# RemoteControlPowerBoard.net
KiCad netlist of a schematic drawn in Altium Designer
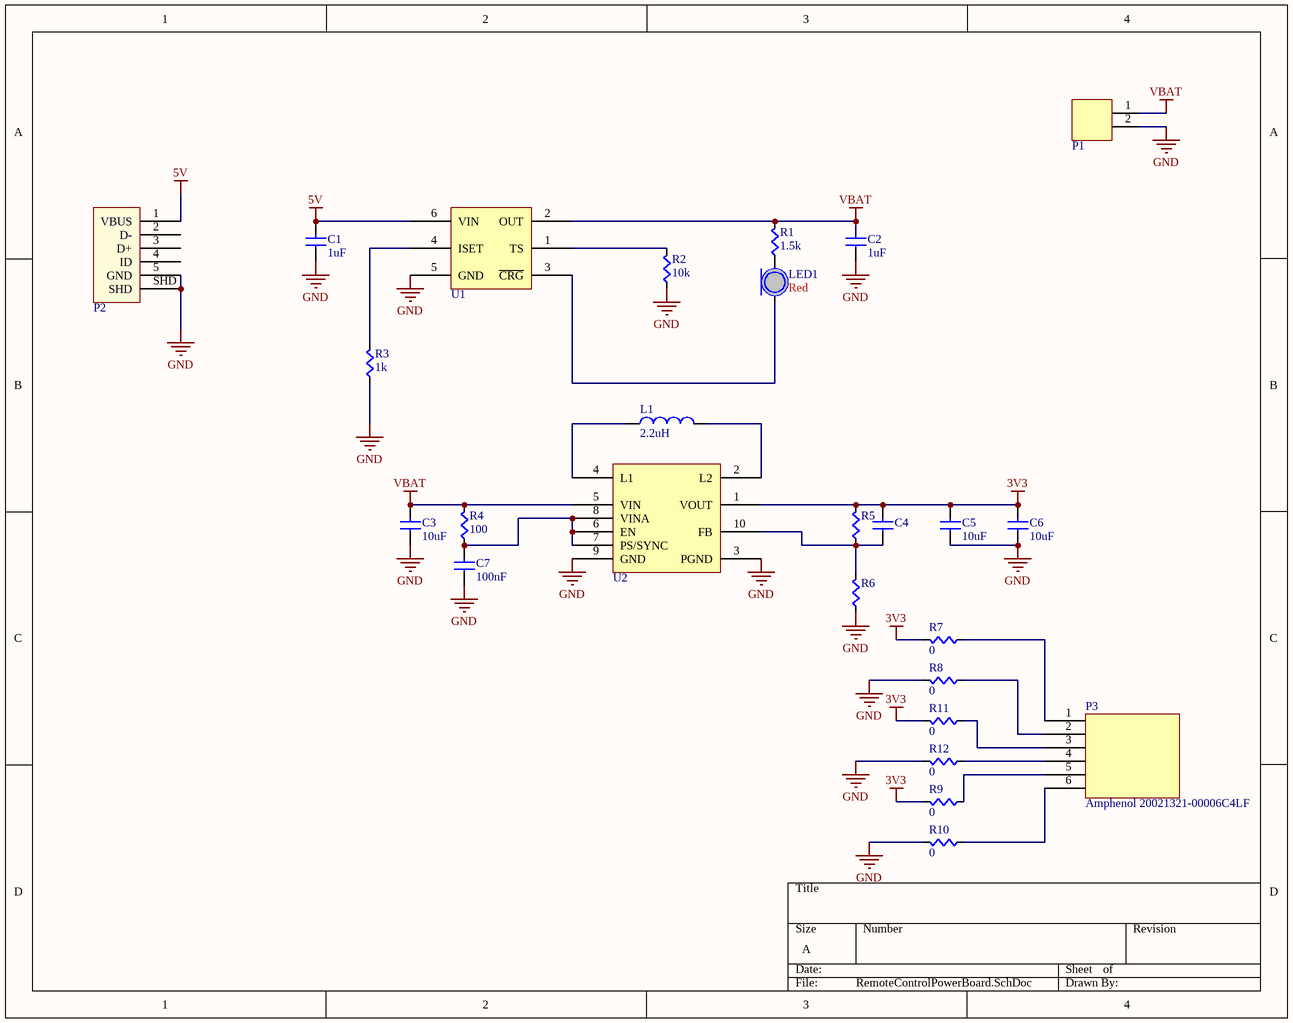
[diagram p0: RemoteControlPowerBoard.SchDoc]

(export (version "E")
  (design (tool "Eeschema 10.0.6"))
  (components
    (comp (ref "C1")
      (value "1uF")
      (footprint "CAPC0603")
      (fields (field (name "Comment") "Cap"))
      (libsource (lib "SubjuGator8") (part "Cap"))
    )
    (comp (ref "C2")
      (value "1uF")
      (footprint "CAPC0603")
      (fields (field (name "Comment") "Cap"))
      (libsource (lib "SubjuGator8") (part "Cap"))
    )
    (comp (ref "C3")
      (value "10uF")
      (footprint "CAPC0603")
      (fields (field (name "Comment") "Cap"))
      (libsource (lib "SubjuGator8") (part "Cap"))
    )
    (comp (ref "C4") (value "Cap") (footprint "CAPC0603") (libsource (lib "SubjuGator8") (part "Cap")))
    (comp (ref "C5")
      (value "10uF")
      (footprint "CAPC0603")
      (fields (field (name "Comment") "Cap"))
      (libsource (lib "SubjuGator8") (part "Cap"))
    )
    (comp (ref "C6")
      (value "10uF")
      (footprint "CAPC0603")
      (fields (field (name "Comment") "Cap"))
      (libsource (lib "SubjuGator8") (part "Cap"))
    )
    (comp (ref "C7")
      (value "100nF")
      (footprint "CAPC0603")
      (fields (field (name "Comment") "Cap"))
      (libsource (lib "SubjuGator8") (part "Cap"))
    )
    (comp (ref "L1")
      (value "LQH3NPZ2R2MMEL")
      (footprint "LQH3NPZ2R2MMEL")
      (fields (field (name "INDUCTANCE") "2.2uH"))
      (libsource (lib "Passives") (part "LQH3NPZ2R2MMEL"))
    )
    (comp (ref "LED1")
      (value "LED")
      (footprint "LED0603")
      (fields (field (name "COLOR") "Red"))
      (libsource (lib "SubjuGator8") (part "LED"))
    )
    (comp (ref "P1")
      (value "2-pin Horz Sherlock")
      (footprint "MOLEX-HDR-1X2-SHERLOCK-HORZ")
      (fields
        (field (name "MANUFACTURER PART NUMBER") "0353630260")
        (field (name "MANUFACTURER") "Molex Inc")
      )
      (libsource (lib "SubjuGator8") (part "MOLEX-HDR-1x2-SHERLOCK_RA"))
    )
    (comp (ref "P2")
      (value "UX60SC-MB-5ST")
      (footprint "UX60SC-MB-5ST")
      (description "USB Mini B Metal Shield SMT")
      (libsource (lib "SubjuGator8") (part "UX60SC-MB-5ST"))
    )
    (comp (ref "P3")
      (value "Amphenol 20021321-00006C4LF")
      (footprint "Amphenol FCI 20021321-00006C4LF - duplicate")
      (description "6 Position Receptacle Connector 0.050\" (1.27mm) Surface Mount Gold")
      (libsource (lib "SubjuGator8") (part "Amphenol FCI 20021321-00006C4LF"))
    )
    (comp (ref "R1")
      (value "1.5k")
      (footprint "RES0603")
      (fields (field (name "Comment") "Res"))
      (libsource (lib "SubjuGator8") (part "Res"))
    )
    (comp (ref "R2")
      (value "10k")
      (footprint "RES0603")
      (fields (field (name "Comment") "Res"))
      (libsource (lib "SubjuGator8") (part "Res"))
    )
    (comp (ref "R3")
      (value "1k")
      (footprint "RES0603")
      (fields (field (name "Comment") "Res"))
      (libsource (lib "SubjuGator8") (part "Res"))
    )
    (comp (ref "R4")
      (value "100")
      (footprint "RES0603")
      (fields (field (name "Comment") "Res"))
      (libsource (lib "SubjuGator8") (part "Res"))
    )
    (comp (ref "R5") (value "Res") (footprint "RES0603") (libsource (lib "SubjuGator8") (part "Res")))
    (comp (ref "R6") (value "Res") (footprint "RES0603") (libsource (lib "SubjuGator8") (part "Res")))
    (comp (ref "R7")
      (value "0")
      (footprint "RES0603")
      (fields (field (name "Comment") "Res"))
      (libsource (lib "SubjuGator8") (part "Res"))
    )
    (comp (ref "R8")
      (value "0")
      (footprint "RES0603")
      (fields (field (name "Comment") "Res"))
      (libsource (lib "SubjuGator8") (part "Res"))
    )
    (comp (ref "R9")
      (value "0")
      (footprint "RES0603")
      (fields (field (name "Comment") "Res"))
      (libsource (lib "SubjuGator8") (part "Res"))
    )
    (comp (ref "R10")
      (value "0")
      (footprint "RES0603")
      (fields (field (name "Comment") "Res"))
      (libsource (lib "SubjuGator8") (part "Res"))
    )
    (comp (ref "R11")
      (value "0")
      (footprint "RES0603")
      (fields (field (name "Comment") "Res"))
      (libsource (lib "SubjuGator8") (part "Res"))
    )
    (comp (ref "R12")
      (value "0")
      (footprint "RES0603")
      (fields (field (name "Comment") "Res"))
      (libsource (lib "SubjuGator8") (part "Res"))
    )
    (comp (ref "U1")
      (value "BQ21040")
      (footprint "BQ21040DBVT")
      (description "IC BAT CHG LI-ION 1 CELL SOT23-6")
      (libsource (lib "ICs") (part "BQ21040"))
    )
    (comp (ref "U2")
      (value "TPS63000DRCR")
      (footprint "TPS63000DRCR")
      (libsource (lib "ICs") (part "TPS63000DRCR"))
    )
  )
  (nets
    (net (code "1") (name "3V3") (class "Default")
      (node (ref "C4") (pin "1") (pinfunction "A_1") (pintype "passive"))
      (node (ref "C5") (pin "1") (pinfunction "A_1") (pintype "passive"))
      (node (ref "C6") (pin "1") (pinfunction "A_1") (pintype "passive"))
      (node (ref "R11") (pin "1") (pinfunction "A_1") (pintype "passive"))
      (node (ref "R5") (pin "1") (pinfunction "A_1") (pintype "passive"))
      (node (ref "R7") (pin "1") (pinfunction "A_1") (pintype "passive"))
      (node (ref "R9") (pin "1") (pinfunction "A_1") (pintype "passive"))
      (node (ref "U2") (pin "1") (pinfunction "VOUT_1") (pintype "passive"))
    )
    (net (code "2") (name "5V") (class "Default")
      (node (ref "C1") (pin "1") (pinfunction "A_1") (pintype "passive"))
      (node (ref "P2") (pin "1") (pinfunction "VBUS_1") (pintype "passive"))
      (node (ref "U1") (pin "6") (pinfunction "VIN_6") (pintype "passive"))
    )
    (net (code "3") (name "GND") (class "Default")
      (node (ref "C1") (pin "2") (pinfunction "B_2") (pintype "passive"))
      (node (ref "C2") (pin "2") (pinfunction "B_2") (pintype "passive"))
      (node (ref "C3") (pin "2") (pinfunction "B_2") (pintype "passive"))
      (node (ref "C5") (pin "2") (pinfunction "B_2") (pintype "passive"))
      (node (ref "C6") (pin "2") (pinfunction "B_2") (pintype "passive"))
      (node (ref "C7") (pin "2") (pinfunction "B_2") (pintype "passive"))
      (node (ref "P1") (pin "2") (pinfunction "2_2") (pintype "passive"))
      (node (ref "P2") (pin "5") (pinfunction "GND_5") (pintype "passive"))
      (node (ref "P2") (pin "SHD") (pinfunction "SHD_SHD") (pintype "passive"))
      (node (ref "R10") (pin "1") (pinfunction "A_1") (pintype "passive"))
      (node (ref "R12") (pin "1") (pinfunction "A_1") (pintype "passive"))
      (node (ref "R2") (pin "2") (pinfunction "B_2") (pintype "passive"))
      (node (ref "R3") (pin "2") (pinfunction "B_2") (pintype "passive"))
      (node (ref "R6") (pin "2") (pinfunction "B_2") (pintype "passive"))
      (node (ref "R8") (pin "1") (pinfunction "A_1") (pintype "passive"))
      (node (ref "U1") (pin "5") (pinfunction "GND_5") (pintype "passive"))
      (node (ref "U2") (pin "3") (pinfunction "PGND_3") (pintype "passive"))
      (node (ref "U2") (pin "9") (pinfunction "GND_9") (pintype "passive"))
    )
    (net (code "4") (name "Net-(C4-B)") (class "Default")
      (node (ref "C4") (pin "2") (pinfunction "B_2") (pintype "passive"))
      (node (ref "R5") (pin "2") (pinfunction "B_2") (pintype "passive"))
      (node (ref "R6") (pin "1") (pinfunction "A_1") (pintype "passive"))
      (node (ref "U2") (pin "10") (pinfunction "FB_10") (pintype "passive"))
    )
    (net (code "5") (name "Net-(C7-A)") (class "Default")
      (node (ref "C7") (pin "1") (pinfunction "A_1") (pintype "passive"))
      (node (ref "R4") (pin "2") (pinfunction "B_2") (pintype "passive"))
      (node (ref "U2") (pin "6") (pinfunction "EN_6") (pintype "passive"))
      (node (ref "U2") (pin "7") (pinfunction "PS/SYNC_7") (pintype "passive"))
      (node (ref "U2") (pin "8") (pinfunction "VINA_8") (pintype "passive"))
    )
    (net (code "6") (name "Net-(L1-A)") (class "Default")
      (node (ref "L1") (pin "1") (pinfunction "A_1") (pintype "passive"))
      (node (ref "U2") (pin "4") (pinfunction "L1_4") (pintype "passive"))
    )
    (net (code "7") (name "Net-(L1-B)") (class "Default")
      (node (ref "L1") (pin "2") (pinfunction "B_2") (pintype "passive"))
      (node (ref "U2") (pin "2") (pinfunction "L2_2") (pintype "passive"))
    )
    (net (code "8") (name "Net-(R1-B)") (class "Default")
      (node (ref "LED1") (pin "A") (pinfunction "A_A") (pintype "passive"))
      (node (ref "R1") (pin "2") (pinfunction "B_2") (pintype "passive"))
    )
    (net (code "9") (name "Net-(R2-A)") (class "Default")
      (node (ref "R2") (pin "1") (pinfunction "A_1") (pintype "passive"))
      (node (ref "U1") (pin "1") (pinfunction "TS_1") (pintype "passive"))
    )
    (net (code "10") (name "Net-(R3-A)") (class "Default")
      (node (ref "R3") (pin "1") (pinfunction "A_1") (pintype "passive"))
      (node (ref "U1") (pin "4") (pinfunction "ISET_4") (pintype "passive"))
    )
    (net (code "11") (name "Net-(R7-B)") (class "Default")
      (node (ref "P3") (pin "1") (pintype "passive"))
      (node (ref "R7") (pin "2") (pinfunction "B_2") (pintype "passive"))
    )
    (net (code "12") (name "Net-(R8-B)") (class "Default")
      (node (ref "P3") (pin "2") (pintype "passive"))
      (node (ref "R8") (pin "2") (pinfunction "B_2") (pintype "passive"))
    )
    (net (code "13") (name "Net-(R9-B)") (class "Default")
      (node (ref "P3") (pin "5") (pintype "passive"))
      (node (ref "R9") (pin "2") (pinfunction "B_2") (pintype "passive"))
    )
    (net (code "14") (name "Net-(R10-B)") (class "Default")
      (node (ref "P3") (pin "6") (pintype "passive"))
      (node (ref "R10") (pin "2") (pinfunction "B_2") (pintype "passive"))
    )
    (net (code "15") (name "Net-(R11-B)") (class "Default")
      (node (ref "P3") (pin "3") (pintype "passive"))
      (node (ref "R11") (pin "2") (pinfunction "B_2") (pintype "passive"))
    )
    (net (code "16") (name "Net-(R12-B)") (class "Default")
      (node (ref "P3") (pin "4") (pintype "passive"))
      (node (ref "R12") (pin "2") (pinfunction "B_2") (pintype "passive"))
    )
    (net (code "17") (name "Net-(U1-~{CRG})") (class "Default")
      (node (ref "LED1") (pin "C") (pinfunction "C_C") (pintype "passive"))
      (node (ref "U1") (pin "3") (pinfunction "~{CRG}_3") (pintype "passive"))
    )
    (net (code "18") (name "VBAT") (class "Default")
      (node (ref "C2") (pin "1") (pinfunction "A_1") (pintype "passive"))
      (node (ref "C3") (pin "1") (pinfunction "A_1") (pintype "passive"))
      (node (ref "P1") (pin "1") (pinfunction "1_1") (pintype "passive"))
      (node (ref "R1") (pin "1") (pinfunction "A_1") (pintype "passive"))
      (node (ref "R4") (pin "1") (pinfunction "A_1") (pintype "passive"))
      (node (ref "U1") (pin "2") (pinfunction "OUT_2") (pintype "passive"))
      (node (ref "U2") (pin "5") (pinfunction "VIN_5") (pintype "passive"))
    )
    (net (code "19") (name "unconnected-(P2-D+-Pad3)") (class "Default")
      (node (ref "P2") (pin "3") (pinfunction "D+_3") (pintype "passive"))
    )
    (net (code "20") (name "unconnected-(P2-D--Pad2)") (class "Default")
      (node (ref "P2") (pin "2") (pinfunction "D-_2") (pintype "passive"))
    )
    (net (code "21") (name "unconnected-(P2-ID-Pad4)") (class "Default")
      (node (ref "P2") (pin "4") (pinfunction "ID_4") (pintype "passive"))
    )
  )
)
